# PWM_PPM_FMU_REV_2A.net
KiCad netlist of a schematic drawn in Altium Designer
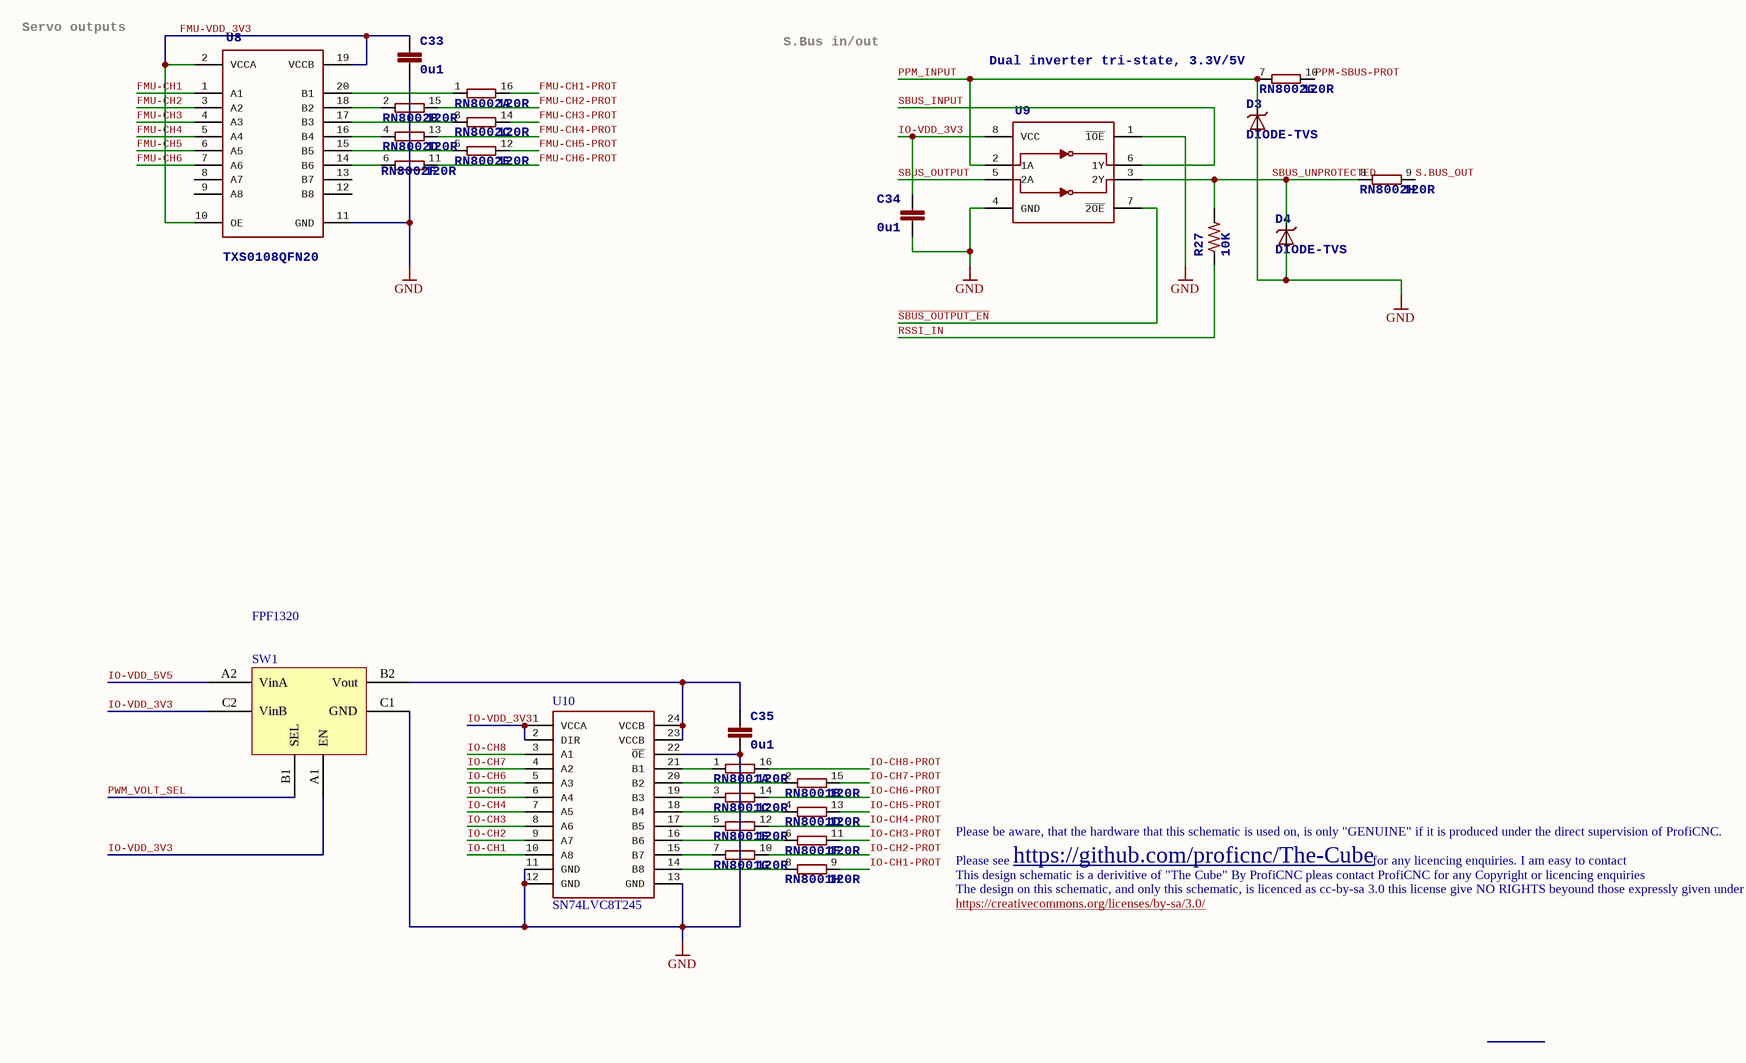
[diagram p0: PWM_PPM_FMU_REV_2A.SchDoc]

(export (version "E")
  (design (tool "Eeschema 10.0.6"))
  (components
    (comp (ref "C33")
      (value "0u1")
      (footprint "0402-CAP")
      (description "CAP CER 0.1UF 16V Y5V 0402")
      (libsource (lib "pixhawk2") (part "CAP0402"))
    )
    (comp (ref "C34")
      (value "0u1")
      (footprint "0402-CAP")
      (description "CAP CER 0.1UF 16V Y5V 0402")
      (libsource (lib "") (part "CAP0402_1"))
    )
    (comp (ref "C35")
      (value "0u1")
      (footprint "0402-CAP")
      (description "CAP CER 0.1UF 16V Y5V 0402")
      (libsource (lib "pixhawk2") (part "CAP0402"))
    )
    (comp (ref "D3")
      (value "DIODE-TVS")
      (footprint "0402-TVS")
      (description "TVS DIODE 14VWM 40VC 0402")
      (libsource (lib "pixhawk2") (part "DIODE-TVS"))
    )
    (comp (ref "D4")
      (value "DIODE-TVS")
      (footprint "0402-TVS")
      (description "TVS DIODE 14VWM 40VC 0402")
      (libsource (lib "pixhawk2") (part "DIODE-TVS"))
    )
    (comp (ref "R27")
      (value "10K")
      (footprint "0402-RES")
      (description "RES 10K OHM 1/16W 1% 0402 SMD")
      (libsource (lib "pixhawk2") (part "RESISTOR0402-RES"))
    )
    (comp (ref "RN8001")
      (value "120R")
      (footprint "EXB2HV")
      (description "RES ARRAY 120 OHM 8 RES 1506")
      (libsource (lib "pixhawk2") (part "8R-NEXB2HV-220R"))
    )
    (comp (ref "RN8002")
      (value "120R")
      (footprint "EXB2HV")
      (description "RES ARRAY 120 OHM 8 RES 1506")
      (libsource (lib "pixhawk2") (part "8R-NEXB2HV-220R"))
    )
    (comp (ref "SW1") (value "FPF1320") (footprint "FPF1320") (libsource (lib "OMD") (part "FPF1320")))
    (comp (ref "U8")
      (value "TXS0108QFN20")
      (footprint "QFN20-RGY")
      (description "IC XLATR VOLT-LVL 8B BDIR 20QFN")
      (libsource (lib "pixhawk2") (part "TXS0108QFN20"))
    )
    (comp (ref "U9")
      (value "Dual inverter tri-state, 3.3V/5V")
      (footprint "TSSOP8_SOT505-2")
      (description "IC INVERTER DUAL 4-INPUT 8TSSOP")
      (libsource (lib "pixhawk2") (part "74LVC2G240-TSSOP-8"))
    )
    (comp (ref "U10")
      (value "SN74LVC8T245")
      (footprint "QFN24-RGY")
      (libsource (lib "3DR") (part "SN74LVC8T245"))
    )
  )
  (nets
    (net (code "1") (name "/FMU-CH1") (class "Default")
      (node (ref "U8") (pin "1") (pinfunction "A1_1") (pintype "passive"))
    )
    (net (code "2") (name "/FMU-CH1-PROT") (class "Default")
      (node (ref "RN8002") (pin "16") (pinfunction "2_16") (pintype "passive"))
    )
    (net (code "3") (name "/FMU-CH2") (class "Default")
      (node (ref "U8") (pin "3") (pinfunction "A2_3") (pintype "passive"))
    )
    (net (code "4") (name "/FMU-CH2-PROT") (class "Default")
      (node (ref "RN8002") (pin "15") (pinfunction "2_15") (pintype "passive"))
    )
    (net (code "5") (name "/FMU-CH3") (class "Default")
      (node (ref "U8") (pin "4") (pinfunction "A3_4") (pintype "passive"))
    )
    (net (code "6") (name "/FMU-CH3-PROT") (class "Default")
      (node (ref "RN8002") (pin "14") (pinfunction "2_14") (pintype "passive"))
    )
    (net (code "7") (name "/FMU-CH4") (class "Default")
      (node (ref "U8") (pin "5") (pinfunction "A4_5") (pintype "passive"))
    )
    (net (code "8") (name "/FMU-CH4-PROT") (class "Default")
      (node (ref "RN8002") (pin "13") (pinfunction "2_13") (pintype "passive"))
    )
    (net (code "9") (name "/FMU-CH5") (class "Default")
      (node (ref "U8") (pin "6") (pinfunction "A5_6") (pintype "passive"))
    )
    (net (code "10") (name "/FMU-CH5-PROT") (class "Default")
      (node (ref "RN8002") (pin "12") (pinfunction "2_12") (pintype "passive"))
    )
    (net (code "11") (name "/FMU-CH6") (class "Default")
      (node (ref "U8") (pin "7") (pinfunction "A6_7") (pintype "passive"))
    )
    (net (code "12") (name "/FMU-CH6-PROT") (class "Default")
      (node (ref "RN8002") (pin "11") (pinfunction "2_11") (pintype "passive"))
    )
    (net (code "13") (name "/FMU-VDD_3V3") (class "Default")
      (node (ref "C33") (pin "P$1") (pinfunction "1_P$1") (pintype "passive"))
      (node (ref "U8") (pin "10") (pinfunction "OE_10") (pintype "passive"))
      (node (ref "U8") (pin "19") (pinfunction "VCCB_19") (pintype "passive"))
      (node (ref "U8") (pin "2") (pinfunction "VCCA_2") (pintype "passive"))
    )
    (net (code "14") (name "/IO-CH1") (class "Default")
      (node (ref "U10") (pin "10") (pinfunction "A8_10") (pintype "passive"))
    )
    (net (code "15") (name "/IO-CH1-PROT") (class "Default")
      (node (ref "RN8001") (pin "9") (pinfunction "2_9") (pintype "passive"))
    )
    (net (code "16") (name "/IO-CH2") (class "Default")
      (node (ref "U10") (pin "9") (pinfunction "A7_9") (pintype "passive"))
    )
    (net (code "17") (name "/IO-CH2-PROT") (class "Default")
      (node (ref "RN8001") (pin "10") (pinfunction "2_10") (pintype "passive"))
    )
    (net (code "18") (name "/IO-CH3") (class "Default")
      (node (ref "U10") (pin "8") (pinfunction "A6_8") (pintype "passive"))
    )
    (net (code "19") (name "/IO-CH3-PROT") (class "Default")
      (node (ref "RN8001") (pin "11") (pinfunction "2_11") (pintype "passive"))
    )
    (net (code "20") (name "/IO-CH4") (class "Default")
      (node (ref "U10") (pin "7") (pinfunction "A5_7") (pintype "passive"))
    )
    (net (code "21") (name "/IO-CH4-PROT") (class "Default")
      (node (ref "RN8001") (pin "12") (pinfunction "2_12") (pintype "passive"))
    )
    (net (code "22") (name "/IO-CH5") (class "Default")
      (node (ref "U10") (pin "6") (pinfunction "A4_6") (pintype "passive"))
    )
    (net (code "23") (name "/IO-CH5-PROT") (class "Default")
      (node (ref "RN8001") (pin "13") (pinfunction "2_13") (pintype "passive"))
    )
    (net (code "24") (name "/IO-CH6") (class "Default")
      (node (ref "U10") (pin "5") (pinfunction "A3_5") (pintype "passive"))
    )
    (net (code "25") (name "/IO-CH6-PROT") (class "Default")
      (node (ref "RN8001") (pin "14") (pinfunction "2_14") (pintype "passive"))
    )
    (net (code "26") (name "/IO-CH7") (class "Default")
      (node (ref "U10") (pin "4") (pinfunction "A2_4") (pintype "passive"))
    )
    (net (code "27") (name "/IO-CH7-PROT") (class "Default")
      (node (ref "RN8001") (pin "15") (pinfunction "2_15") (pintype "passive"))
    )
    (net (code "28") (name "/IO-CH8") (class "Default")
      (node (ref "U10") (pin "3") (pinfunction "A1_3") (pintype "passive"))
    )
    (net (code "29") (name "/IO-CH8-PROT") (class "Default")
      (node (ref "RN8001") (pin "16") (pinfunction "2_16") (pintype "passive"))
    )
    (net (code "30") (name "/IO-VDD_3V3") (class "Default")
      (node (ref "C34") (pin "P$1") (pinfunction "1_P$1") (pintype "passive"))
      (node (ref "SW1") (pin "A1") (pinfunction "EN_A1") (pintype "passive"))
      (node (ref "SW1") (pin "C2") (pinfunction "VinB_C2") (pintype "passive"))
      (node (ref "U10") (pin "1") (pinfunction "VCCA_1") (pintype "passive"))
      (node (ref "U10") (pin "2") (pinfunction "DIR_2") (pintype "passive"))
      (node (ref "U9") (pin "8") (pinfunction "VCC_8") (pintype "open_emitter"))
    )
    (net (code "31") (name "/IO-VDD_5V5") (class "Default")
      (node (ref "SW1") (pin "A2") (pinfunction "VinA_A2") (pintype "passive"))
    )
    (net (code "32") (name "/PPM-SBUS-PROT") (class "Default")
      (node (ref "RN8002") (pin "10") (pinfunction "2_10") (pintype "passive"))
    )
    (net (code "33") (name "/PPM_INPUT") (class "Default")
      (node (ref "D3") (pin "C") (pinfunction "C_C") (pintype "passive"))
      (node (ref "RN8002") (pin "7") (pinfunction "1_7") (pintype "passive"))
      (node (ref "U9") (pin "2") (pinfunction "1A_2") (pintype "passive"))
    )
    (net (code "34") (name "/PWM_VOLT_SEL") (class "Default")
      (node (ref "SW1") (pin "B1") (pinfunction "SEL_B1") (pintype "passive"))
    )
    (net (code "35") (name "/RSSI_IN") (class "Default")
      (node (ref "R27") (pin "P$1") (pinfunction "1_P$1") (pintype "passive"))
    )
    (net (code "36") (name "/S.BUS_OUT") (class "Default")
      (node (ref "RN8002") (pin "9") (pinfunction "2_9") (pintype "passive"))
    )
    (net (code "37") (name "/SBUS_INPUT") (class "Default")
      (node (ref "U9") (pin "6") (pinfunction "1Y_6") (pintype "passive"))
    )
    (net (code "38") (name "/SBUS_OUTPUT") (class "Default")
      (node (ref "U9") (pin "5") (pinfunction "2A_5") (pintype "passive"))
    )
    (net (code "39") (name "/SBUS_UNPROTECTED") (class "Default")
      (node (ref "D4") (pin "C") (pinfunction "C_C") (pintype "passive"))
      (node (ref "R27") (pin "P$2") (pinfunction "2_P$2") (pintype "passive"))
      (node (ref "RN8002") (pin "8") (pinfunction "1_8") (pintype "passive"))
      (node (ref "U9") (pin "3") (pinfunction "2Y_3") (pintype "passive"))
    )
    (net (code "40") (name "/~{SBUS_OUTPUT_EN}") (class "Default")
      (node (ref "U9") (pin "7") (pinfunction "~{2OE}_7") (pintype "passive"))
    )
    (net (code "41") (name "GND") (class "Default")
      (node (ref "C33") (pin "P$2") (pinfunction "2_P$2") (pintype "passive"))
      (node (ref "C34") (pin "P$2") (pinfunction "2_P$2") (pintype "passive"))
      (node (ref "C35") (pin "P$2") (pinfunction "2_P$2") (pintype "passive"))
      (node (ref "D3") (pin "A") (pinfunction "A_A") (pintype "passive"))
      (node (ref "D4") (pin "A") (pinfunction "A_A") (pintype "passive"))
      (node (ref "SW1") (pin "C1") (pinfunction "GND_C1") (pintype "passive"))
      (node (ref "U10") (pin "11") (pinfunction "GND_11") (pintype "open_emitter"))
      (node (ref "U10") (pin "12") (pinfunction "GND_12") (pintype "open_emitter"))
      (node (ref "U10") (pin "13") (pinfunction "GND_13") (pintype "open_emitter"))
      (node (ref "U10") (pin "22") (pinfunction "~{OE}_22") (pintype "passive"))
      (node (ref "U8") (pin "11") (pinfunction "GND_11") (pintype "open_emitter"))
      (node (ref "U9") (pin "1") (pinfunction "~{1OE}_1") (pintype "passive"))
      (node (ref "U9") (pin "4") (pinfunction "GND_4") (pintype "open_emitter"))
    )
    (net (code "42") (name "Net-(C35-1)") (class "Default")
      (node (ref "C35") (pin "P$1") (pinfunction "1_P$1") (pintype "passive"))
      (node (ref "SW1") (pin "B2") (pinfunction "Vout_B2") (pintype "passive"))
      (node (ref "U10") (pin "23") (pinfunction "VCCB_23") (pintype "passive"))
      (node (ref "U10") (pin "24") (pinfunction "VCCB_24") (pintype "passive"))
    )
    (net (code "43") (name "Net-(RN8001B-1)") (class "Default")
      (node (ref "RN8001") (pin "2") (pinfunction "1_2") (pintype "passive"))
      (node (ref "U10") (pin "20") (pinfunction "B2_20") (pintype "passive"))
    )
    (net (code "44") (name "Net-(RN8001C-1)") (class "Default")
      (node (ref "RN8001") (pin "3") (pinfunction "1_3") (pintype "passive"))
      (node (ref "U10") (pin "19") (pinfunction "B3_19") (pintype "passive"))
    )
    (net (code "45") (name "Net-(RN8001D-1)") (class "Default")
      (node (ref "RN8001") (pin "4") (pinfunction "1_4") (pintype "passive"))
      (node (ref "U10") (pin "18") (pinfunction "B4_18") (pintype "passive"))
    )
    (net (code "46") (name "Net-(RN8001E-1)") (class "Default")
      (node (ref "RN8001") (pin "5") (pinfunction "1_5") (pintype "passive"))
      (node (ref "U10") (pin "17") (pinfunction "B5_17") (pintype "passive"))
    )
    (net (code "47") (name "Net-(RN8001F-1)") (class "Default")
      (node (ref "RN8001") (pin "6") (pinfunction "1_6") (pintype "passive"))
      (node (ref "U10") (pin "16") (pinfunction "B6_16") (pintype "passive"))
    )
    (net (code "48") (name "Net-(RN8001G-1)") (class "Default")
      (node (ref "RN8001") (pin "7") (pinfunction "1_7") (pintype "passive"))
      (node (ref "U10") (pin "15") (pinfunction "B7_15") (pintype "passive"))
    )
    (net (code "49") (name "Net-(RN8001H-1)") (class "Default")
      (node (ref "RN8001") (pin "8") (pinfunction "1_8") (pintype "passive"))
      (node (ref "U10") (pin "14") (pinfunction "B8_14") (pintype "passive"))
    )
    (net (code "50") (name "Net-(RN8002B-1)") (class "Default")
      (node (ref "RN8002") (pin "2") (pinfunction "1_2") (pintype "passive"))
      (node (ref "U8") (pin "18") (pinfunction "B2_18") (pintype "passive"))
    )
    (net (code "51") (name "Net-(RN8002C-1)") (class "Default")
      (node (ref "RN8002") (pin "3") (pinfunction "1_3") (pintype "passive"))
      (node (ref "U8") (pin "17") (pinfunction "B3_17") (pintype "passive"))
    )
    (net (code "52") (name "Net-(RN8002D-1)") (class "Default")
      (node (ref "RN8002") (pin "4") (pinfunction "1_4") (pintype "passive"))
      (node (ref "U8") (pin "16") (pinfunction "B4_16") (pintype "passive"))
    )
    (net (code "53") (name "Net-(RN8002E-1)") (class "Default")
      (node (ref "RN8002") (pin "5") (pinfunction "1_5") (pintype "passive"))
      (node (ref "U8") (pin "15") (pinfunction "B5_15") (pintype "passive"))
    )
    (net (code "54") (name "Net-(RN8002F-1)") (class "Default")
      (node (ref "RN8002") (pin "6") (pinfunction "1_6") (pintype "passive"))
      (node (ref "U8") (pin "14") (pinfunction "B6_14") (pintype "passive"))
    )
    (net (code "55") (name "Net-(U8-B1)") (class "Default")
      (node (ref "RN8002") (pin "1") (pinfunction "1_1") (pintype "passive"))
      (node (ref "U8") (pin "20") (pinfunction "B1_20") (pintype "passive"))
    )
    (net (code "56") (name "Net-(U10-B1)") (class "Default")
      (node (ref "RN8001") (pin "1") (pinfunction "1_1") (pintype "passive"))
      (node (ref "U10") (pin "21") (pinfunction "B1_21") (pintype "passive"))
    )
    (net (code "57") (name "unconnected-(U8-A7-Pad8)") (class "Default")
      (node (ref "U8") (pin "8") (pinfunction "A7_8") (pintype "passive"))
    )
    (net (code "58") (name "unconnected-(U8-A8-Pad9)") (class "Default")
      (node (ref "U8") (pin "9") (pinfunction "A8_9") (pintype "passive"))
    )
    (net (code "59") (name "unconnected-(U8-B7-Pad13)") (class "Default")
      (node (ref "U8") (pin "13") (pinfunction "B7_13") (pintype "passive"))
    )
    (net (code "60") (name "unconnected-(U8-B8-Pad12)") (class "Default")
      (node (ref "U8") (pin "12") (pinfunction "B8_12") (pintype "passive"))
    )
  )
)
